# Periph.net
KiCad netlist of a schematic drawn in Altium Designer
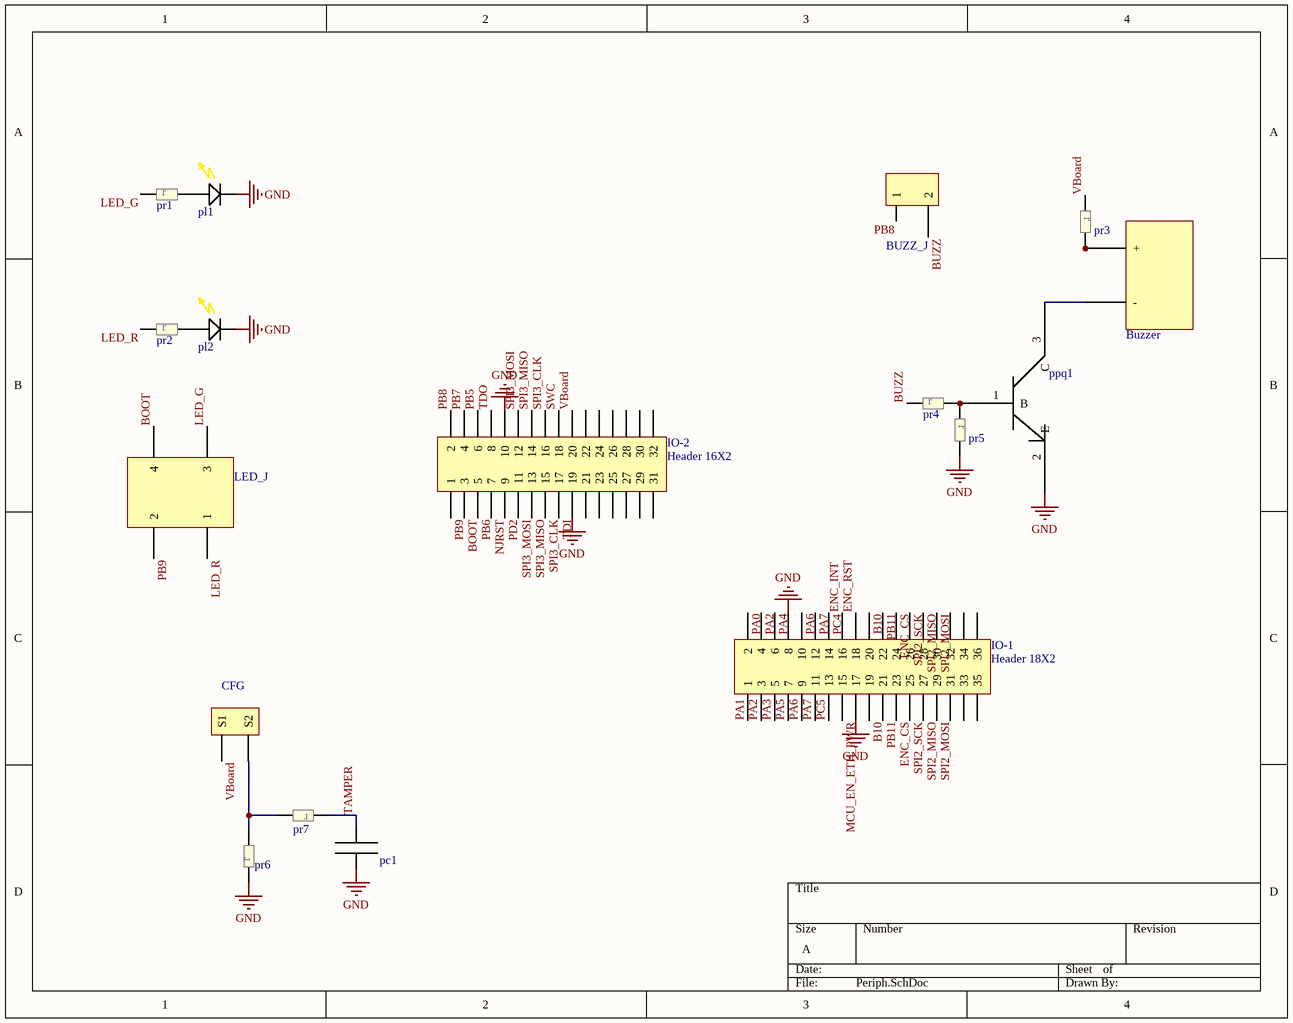
[diagram p0: Periph.SchDoc]

(export (version "E")
  (design (tool "Eeschema 10.0.6"))
  (components
    (comp (ref "Buzzer")
      (value "LED")
      (footprint "ABR_BUZZER_9MM_3D")
      (libsource (lib "abr_led_dip") (part "abr_buzzer"))
    )
    (comp (ref "BUZZ_J")
      (value "pin header 2mm")
      (footprint "abr_ph_2x1_2mm_3d_male")
      (libsource (lib "abr_ph_2mm_96_02") (part "abr_2x1_2mm"))
    )
    (comp (ref "CFG")
      (value "switch")
      (footprint "abr_sw_tact_3d")
      (libsource (lib "abr_switch") (part "abr_switch_tact"))
    )
    (comp (ref "IO-1")
      (value "Header 18X2")
      (footprint "HDR2X18")
      (description "Header, 18-Pin, Dual row")
      (fields (field (name "PUBLISHER") "Altium Limited"))
      (libsource (lib "Miscellaneous Connectors") (part "Header 18X2"))
    )
    (comp (ref "IO-2")
      (value "Header 16X2")
      (footprint "HDR2X16")
      (description "Header, 16-Pin, Dual row")
      (fields (field (name "PUBLISHER") "Altium Limited"))
      (libsource (lib "Miscellaneous Connectors") (part "Header 16X2"))
    )
    (comp (ref "LED_J")
      (value "pin header 2mm")
      (footprint "abr_ph_2x2_2mm_3d_male")
      (libsource (lib "abr_ph_2mm_96_02") (part "abr_2x2_2mm"))
    )
    (comp (ref "pc1")
      (value "100nf")
      (footprint "abr_cap_0805_3d")
      (libsource (lib "abr_smd_0805_all") (part "abr_cap_0805"))
    )
    (comp (ref "pl1")
      (value "smd-0805")
      (footprint "abr_led_g_0805_3d")
      (libsource (lib "abr_smd_0805_all") (part "abr_led_0805"))
    )
    (comp (ref "pl2")
      (value "smd-0805")
      (footprint "abr_led_r_0805_3d")
      (libsource (lib "abr_smd_0805_all") (part "abr_led_0805"))
    )
    (comp (ref "ppq1")
      (value "transistor")
      (footprint "abr_fp_sot-23_3d")
      (libsource (lib "abr_transistor_smd") (part "abr_bc847"))
    )
    (comp (ref "pr1")
      (value "2.2K")
      (footprint "abr_res_0805_3d")
      (libsource (lib "") (part "abr_res_0805_2"))
    )
    (comp (ref "pr2")
      (value "2.2K")
      (footprint "abr_res_0805_3d")
      (libsource (lib "") (part "abr_res_0805_2"))
    )
    (comp (ref "pr3")
      (value "2.2K")
      (footprint "abr_res_0805_3d")
      (libsource (lib "abr_smd_0805_all") (part "abr_res_0805"))
    )
    (comp (ref "pr4")
      (value "2.2K")
      (footprint "abr_res_0805_3d")
      (libsource (lib "") (part "abr_res_0805_2"))
    )
    (comp (ref "pr5")
      (value "2.2K")
      (footprint "abr_res_0805_3d")
      (libsource (lib "abr_smd_0805_all") (part "abr_res_0805"))
    )
    (comp (ref "pr6")
      (value "100K")
      (footprint "abr_res_0805_3d")
      (libsource (lib "") (part "abr_res_0805_3"))
    )
    (comp (ref "pr7") (value "1k") (footprint "abr_res_0805_3d") (libsource (lib "") (part "abr_res_0805_1")))
  )
  (nets
    (net (code "1") (name "/B10") (class "Default")
      (node (ref "IO-1") (pin "19") (pinfunction "19_19") (pintype "passive"))
      (node (ref "IO-1") (pin "20") (pinfunction "20_20") (pintype "passive"))
    )
    (net (code "2") (name "/BOOT") (class "Default")
      (node (ref "IO-2") (pin "3") (pinfunction "3_3") (pintype "passive"))
      (node (ref "LED_J") (pin "4") (pinfunction "4_4") (pintype "passive"))
    )
    (net (code "3") (name "/BUZZ") (class "Default")
      (node (ref "BUZZ_J") (pin "2") (pinfunction "2_2") (pintype "passive"))
      (node (ref "pr4") (pin "0") (pinfunction "0_0") (pintype "passive"))
    )
    (net (code "4") (name "/ENC_CS") (class "Default")
      (node (ref "IO-1") (pin "23") (pinfunction "23_23") (pintype "passive"))
      (node (ref "IO-1") (pin "24") (pinfunction "24_24") (pintype "passive"))
    )
    (net (code "5") (name "/ENC_INT") (class "Default")
      (node (ref "IO-1") (pin "16") (pinfunction "16_16") (pintype "passive"))
    )
    (net (code "6") (name "/ENC_RST") (class "Default")
      (node (ref "IO-1") (pin "18") (pinfunction "18_18") (pintype "passive"))
    )
    (net (code "7") (name "/LED_G") (class "Default")
      (node (ref "LED_J") (pin "3") (pinfunction "3_3") (pintype "passive"))
      (node (ref "pr1") (pin "0") (pinfunction "0_0") (pintype "passive"))
    )
    (net (code "8") (name "/LED_R") (class "Default")
      (node (ref "LED_J") (pin "1") (pinfunction "1_1") (pintype "passive"))
      (node (ref "pr2") (pin "0") (pinfunction "0_0") (pintype "passive"))
    )
    (net (code "9") (name "/MCU_EN_ETH_PWR") (class "Default")
      (node (ref "IO-1") (pin "15") (pinfunction "15_15") (pintype "passive"))
    )
    (net (code "10") (name "/NJRST") (class "Default")
      (node (ref "IO-2") (pin "7") (pinfunction "7_7") (pintype "passive"))
    )
    (net (code "11") (name "/PA0") (class "Default")
      (node (ref "IO-1") (pin "2") (pinfunction "2_2") (pintype "passive"))
    )
    (net (code "12") (name "/PA1") (class "Default")
      (node (ref "IO-1") (pin "1") (pinfunction "1_1") (pintype "passive"))
    )
    (net (code "13") (name "/PA2") (class "Default")
      (node (ref "IO-1") (pin "3") (pinfunction "3_3") (pintype "passive"))
      (node (ref "IO-1") (pin "4") (pinfunction "4_4") (pintype "passive"))
    )
    (net (code "14") (name "/PA3") (class "Default")
      (node (ref "IO-1") (pin "5") (pinfunction "5_5") (pintype "passive"))
    )
    (net (code "15") (name "/PA4") (class "Default")
      (node (ref "IO-1") (pin "6") (pinfunction "6_6") (pintype "passive"))
    )
    (net (code "16") (name "/PA5") (class "Default")
      (node (ref "IO-1") (pin "7") (pinfunction "7_7") (pintype "passive"))
    )
    (net (code "17") (name "/PA6") (class "Default")
      (node (ref "IO-1") (pin "10") (pinfunction "10_10") (pintype "passive"))
      (node (ref "IO-1") (pin "9") (pinfunction "9_9") (pintype "passive"))
    )
    (net (code "18") (name "/PA7") (class "Default")
      (node (ref "IO-1") (pin "11") (pinfunction "11_11") (pintype "passive"))
      (node (ref "IO-1") (pin "12") (pinfunction "12_12") (pintype "passive"))
    )
    (net (code "19") (name "/PB5") (class "Default")
      (node (ref "IO-2") (pin "6") (pinfunction "6_6") (pintype "passive"))
    )
    (net (code "20") (name "/PB6") (class "Default")
      (node (ref "IO-2") (pin "5") (pinfunction "5_5") (pintype "passive"))
    )
    (net (code "21") (name "/PB7") (class "Default")
      (node (ref "IO-2") (pin "4") (pinfunction "4_4") (pintype "passive"))
    )
    (net (code "22") (name "/PB8") (class "Default")
      (node (ref "BUZZ_J") (pin "1") (pinfunction "1_1") (pintype "passive"))
      (node (ref "IO-2") (pin "2") (pinfunction "2_2") (pintype "passive"))
    )
    (net (code "23") (name "/PB9") (class "Default")
      (node (ref "IO-2") (pin "1") (pinfunction "1_1") (pintype "passive"))
      (node (ref "LED_J") (pin "2") (pinfunction "2_2") (pintype "passive"))
    )
    (net (code "24") (name "/PB11") (class "Default")
      (node (ref "IO-1") (pin "21") (pinfunction "21_21") (pintype "passive"))
      (node (ref "IO-1") (pin "22") (pinfunction "22_22") (pintype "passive"))
    )
    (net (code "25") (name "/PC4") (class "Default")
      (node (ref "IO-1") (pin "14") (pinfunction "14_14") (pintype "passive"))
    )
    (net (code "26") (name "/PC5") (class "Default")
      (node (ref "IO-1") (pin "13") (pinfunction "13_13") (pintype "passive"))
    )
    (net (code "27") (name "/PD2") (class "Default")
      (node (ref "IO-2") (pin "9") (pinfunction "9_9") (pintype "passive"))
    )
    (net (code "28") (name "/SPI2_MISO") (class "Default")
      (node (ref "IO-1") (pin "27") (pinfunction "27_27") (pintype "passive"))
      (node (ref "IO-1") (pin "28") (pinfunction "28_28") (pintype "passive"))
    )
    (net (code "29") (name "/SPI2_MOSI") (class "Default")
      (node (ref "IO-1") (pin "29") (pinfunction "29_29") (pintype "passive"))
      (node (ref "IO-1") (pin "30") (pinfunction "30_30") (pintype "passive"))
    )
    (net (code "30") (name "/SPI2_SCK") (class "Default")
      (node (ref "IO-1") (pin "25") (pinfunction "25_25") (pintype "passive"))
      (node (ref "IO-1") (pin "26") (pinfunction "26_26") (pintype "passive"))
    )
    (net (code "31") (name "/SPI3_CLK") (class "Default")
      (node (ref "IO-2") (pin "15") (pinfunction "15_15") (pintype "passive"))
      (node (ref "IO-2") (pin "16") (pinfunction "16_16") (pintype "passive"))
    )
    (net (code "32") (name "/SPI3_MISO") (class "Default")
      (node (ref "IO-2") (pin "13") (pinfunction "13_13") (pintype "passive"))
      (node (ref "IO-2") (pin "14") (pinfunction "14_14") (pintype "passive"))
    )
    (net (code "33") (name "/SPI3_MOSI") (class "Default")
      (node (ref "IO-2") (pin "11") (pinfunction "11_11") (pintype "passive"))
      (node (ref "IO-2") (pin "12") (pinfunction "12_12") (pintype "passive"))
    )
    (net (code "34") (name "/SWC") (class "Default")
      (node (ref "IO-2") (pin "18") (pinfunction "18_18") (pintype "passive"))
    )
    (net (code "35") (name "/TAMPER") (class "Default")
      (node (ref "pc1") (pin "1") (pinfunction "10_1") (pintype "passive"))
      (node (ref "pr7") (pin "0") (pinfunction "0_0") (pintype "passive"))
    )
    (net (code "36") (name "/TDI") (class "Default")
      (node (ref "IO-2") (pin "17") (pinfunction "17_17") (pintype "passive"))
    )
    (net (code "37") (name "/TDO") (class "Default")
      (node (ref "IO-2") (pin "8") (pinfunction "8_8") (pintype "passive"))
    )
    (net (code "38") (name "/VBoard") (class "Default")
      (node (ref "CFG") (pin "1") (pinfunction "S1_1") (pintype "passive"))
      (node (ref "IO-2") (pin "20") (pinfunction "20_20") (pintype "passive"))
      (node (ref "pr3") (pin "0") (pinfunction "0_0") (pintype "passive"))
    )
    (net (code "39") (name "GND") (class "Default")
      (node (ref "IO-1") (pin "17") (pinfunction "17_17") (pintype "passive"))
      (node (ref "IO-1") (pin "8") (pinfunction "8_8") (pintype "passive"))
      (node (ref "IO-2") (pin "10") (pinfunction "10_10") (pintype "passive"))
      (node (ref "IO-2") (pin "19") (pinfunction "19_19") (pintype "passive"))
      (node (ref "pc1") (pin "0") (pinfunction "2_0") (pintype "passive"))
      (node (ref "pl1") (pin "1") (pinfunction "1_1") (pintype "passive"))
      (node (ref "pl2") (pin "1") (pinfunction "1_1") (pintype "passive"))
      (node (ref "ppq1") (pin "2") (pinfunction "E_2") (pintype "passive"))
      (node (ref "pr5") (pin "1") (pinfunction "0_1") (pintype "passive"))
      (node (ref "pr6") (pin "0") (pinfunction "0_0") (pintype "passive"))
    )
    (net (code "40") (name "Net-(Buzzer-+)") (class "Default")
      (node (ref "Buzzer") (pin "1") (pinfunction "+_1") (pintype "passive"))
      (node (ref "pr3") (pin "1") (pinfunction "0_1") (pintype "passive"))
    )
    (net (code "41") (name "Net-(Buzzer--)") (class "Default")
      (node (ref "Buzzer") (pin "2") (pinfunction "-_2") (pintype "passive"))
      (node (ref "ppq1") (pin "3") (pinfunction "C_3") (pintype "passive"))
    )
    (net (code "42") (name "Net-(CFG-S2)") (class "Default")
      (node (ref "CFG") (pin "2") (pinfunction "S2_2") (pintype "passive"))
      (node (ref "pr6") (pin "1") (pinfunction "0_1") (pintype "passive"))
      (node (ref "pr7") (pin "1") (pinfunction "0_1") (pintype "passive"))
    )
    (net (code "43") (name "Net-(pl1-15)") (class "Default")
      (node (ref "pl1") (pin "0") (pinfunction "15_0") (pintype "passive"))
      (node (ref "pr1") (pin "1") (pinfunction "0_1") (pintype "passive"))
    )
    (net (code "44") (name "Net-(pl2-15)") (class "Default")
      (node (ref "pl2") (pin "0") (pinfunction "15_0") (pintype "passive"))
      (node (ref "pr2") (pin "1") (pinfunction "0_1") (pintype "passive"))
    )
    (net (code "45") (name "Net-(ppq1-B)") (class "Default")
      (node (ref "ppq1") (pin "1") (pinfunction "B_1") (pintype "passive"))
      (node (ref "pr4") (pin "1") (pinfunction "0_1") (pintype "passive"))
      (node (ref "pr5") (pin "0") (pinfunction "0_0") (pintype "passive"))
    )
    (net (code "46") (name "unconnected-(IO-1-Pad31)") (class "Default")
      (node (ref "IO-1") (pin "31") (pinfunction "31_31") (pintype "passive"))
    )
    (net (code "47") (name "unconnected-(IO-1-Pad32)") (class "Default")
      (node (ref "IO-1") (pin "32") (pinfunction "32_32") (pintype "passive"))
    )
    (net (code "48") (name "unconnected-(IO-1-Pad33)") (class "Default")
      (node (ref "IO-1") (pin "33") (pinfunction "33_33") (pintype "passive"))
    )
    (net (code "49") (name "unconnected-(IO-1-Pad34)") (class "Default")
      (node (ref "IO-1") (pin "34") (pinfunction "34_34") (pintype "passive"))
    )
    (net (code "50") (name "unconnected-(IO-1-Pad35)") (class "Default")
      (node (ref "IO-1") (pin "35") (pinfunction "35_35") (pintype "passive"))
    )
    (net (code "51") (name "unconnected-(IO-1-Pad36)") (class "Default")
      (node (ref "IO-1") (pin "36") (pinfunction "36_36") (pintype "passive"))
    )
    (net (code "52") (name "unconnected-(IO-2-Pad21)") (class "Default")
      (node (ref "IO-2") (pin "21") (pinfunction "21_21") (pintype "passive"))
    )
    (net (code "53") (name "unconnected-(IO-2-Pad22)") (class "Default")
      (node (ref "IO-2") (pin "22") (pinfunction "22_22") (pintype "passive"))
    )
    (net (code "54") (name "unconnected-(IO-2-Pad23)") (class "Default")
      (node (ref "IO-2") (pin "23") (pinfunction "23_23") (pintype "passive"))
    )
    (net (code "55") (name "unconnected-(IO-2-Pad24)") (class "Default")
      (node (ref "IO-2") (pin "24") (pinfunction "24_24") (pintype "passive"))
    )
    (net (code "56") (name "unconnected-(IO-2-Pad25)") (class "Default")
      (node (ref "IO-2") (pin "25") (pinfunction "25_25") (pintype "passive"))
    )
    (net (code "57") (name "unconnected-(IO-2-Pad26)") (class "Default")
      (node (ref "IO-2") (pin "26") (pinfunction "26_26") (pintype "passive"))
    )
    (net (code "58") (name "unconnected-(IO-2-Pad27)") (class "Default")
      (node (ref "IO-2") (pin "27") (pinfunction "27_27") (pintype "passive"))
    )
    (net (code "59") (name "unconnected-(IO-2-Pad28)") (class "Default")
      (node (ref "IO-2") (pin "28") (pinfunction "28_28") (pintype "passive"))
    )
    (net (code "60") (name "unconnected-(IO-2-Pad29)") (class "Default")
      (node (ref "IO-2") (pin "29") (pinfunction "29_29") (pintype "passive"))
    )
    (net (code "61") (name "unconnected-(IO-2-Pad30)") (class "Default")
      (node (ref "IO-2") (pin "30") (pinfunction "30_30") (pintype "passive"))
    )
    (net (code "62") (name "unconnected-(IO-2-Pad31)") (class "Default")
      (node (ref "IO-2") (pin "31") (pinfunction "31_31") (pintype "passive"))
    )
    (net (code "63") (name "unconnected-(IO-2-Pad32)") (class "Default")
      (node (ref "IO-2") (pin "32") (pinfunction "32_32") (pintype "passive"))
    )
  )
)
